# Edin_Usher_V2_0_discreto.net
KiCad netlist of a schematic drawn in EAGLE
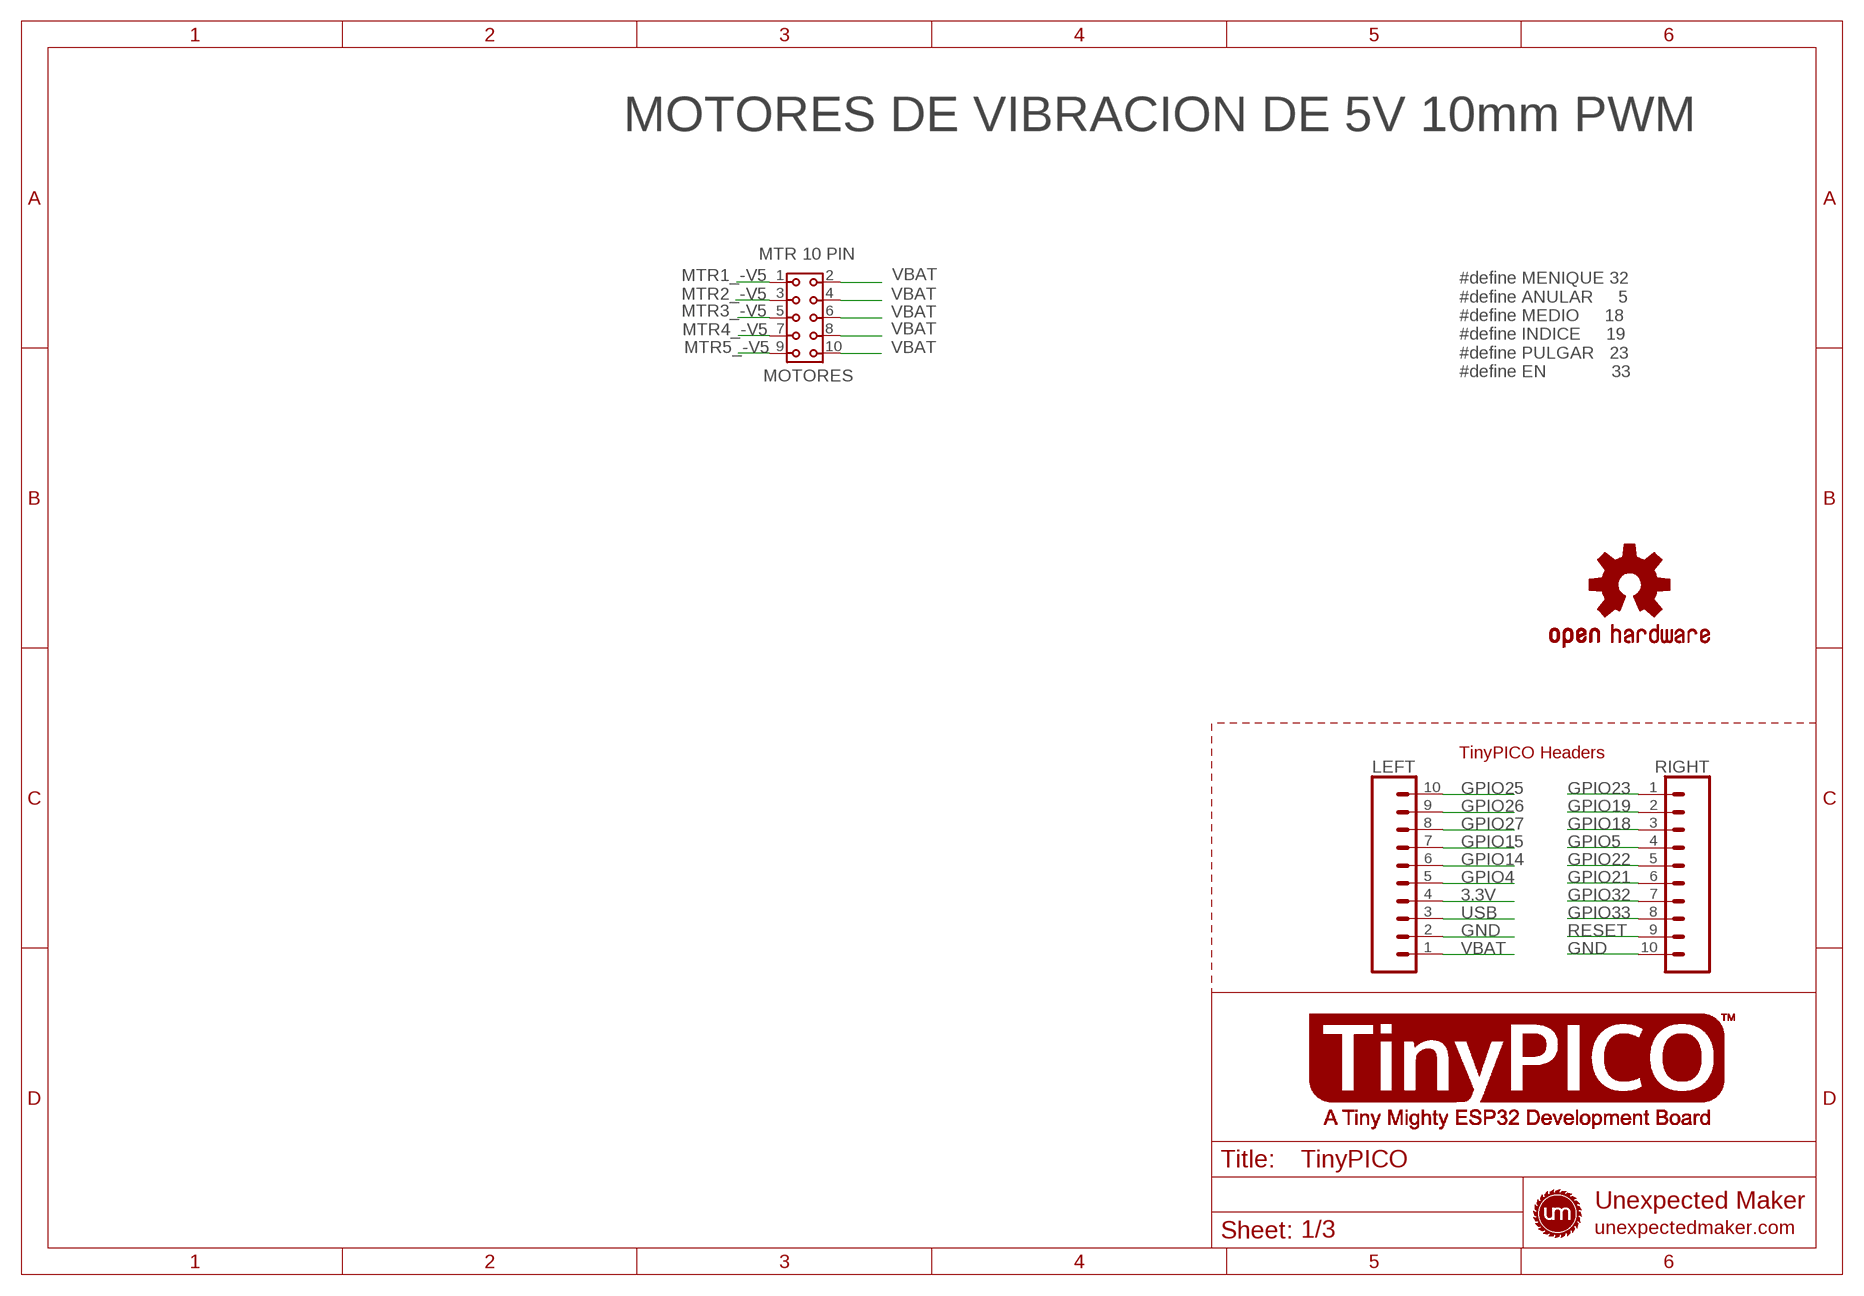
[diagram p0: schematic, sheet 1]
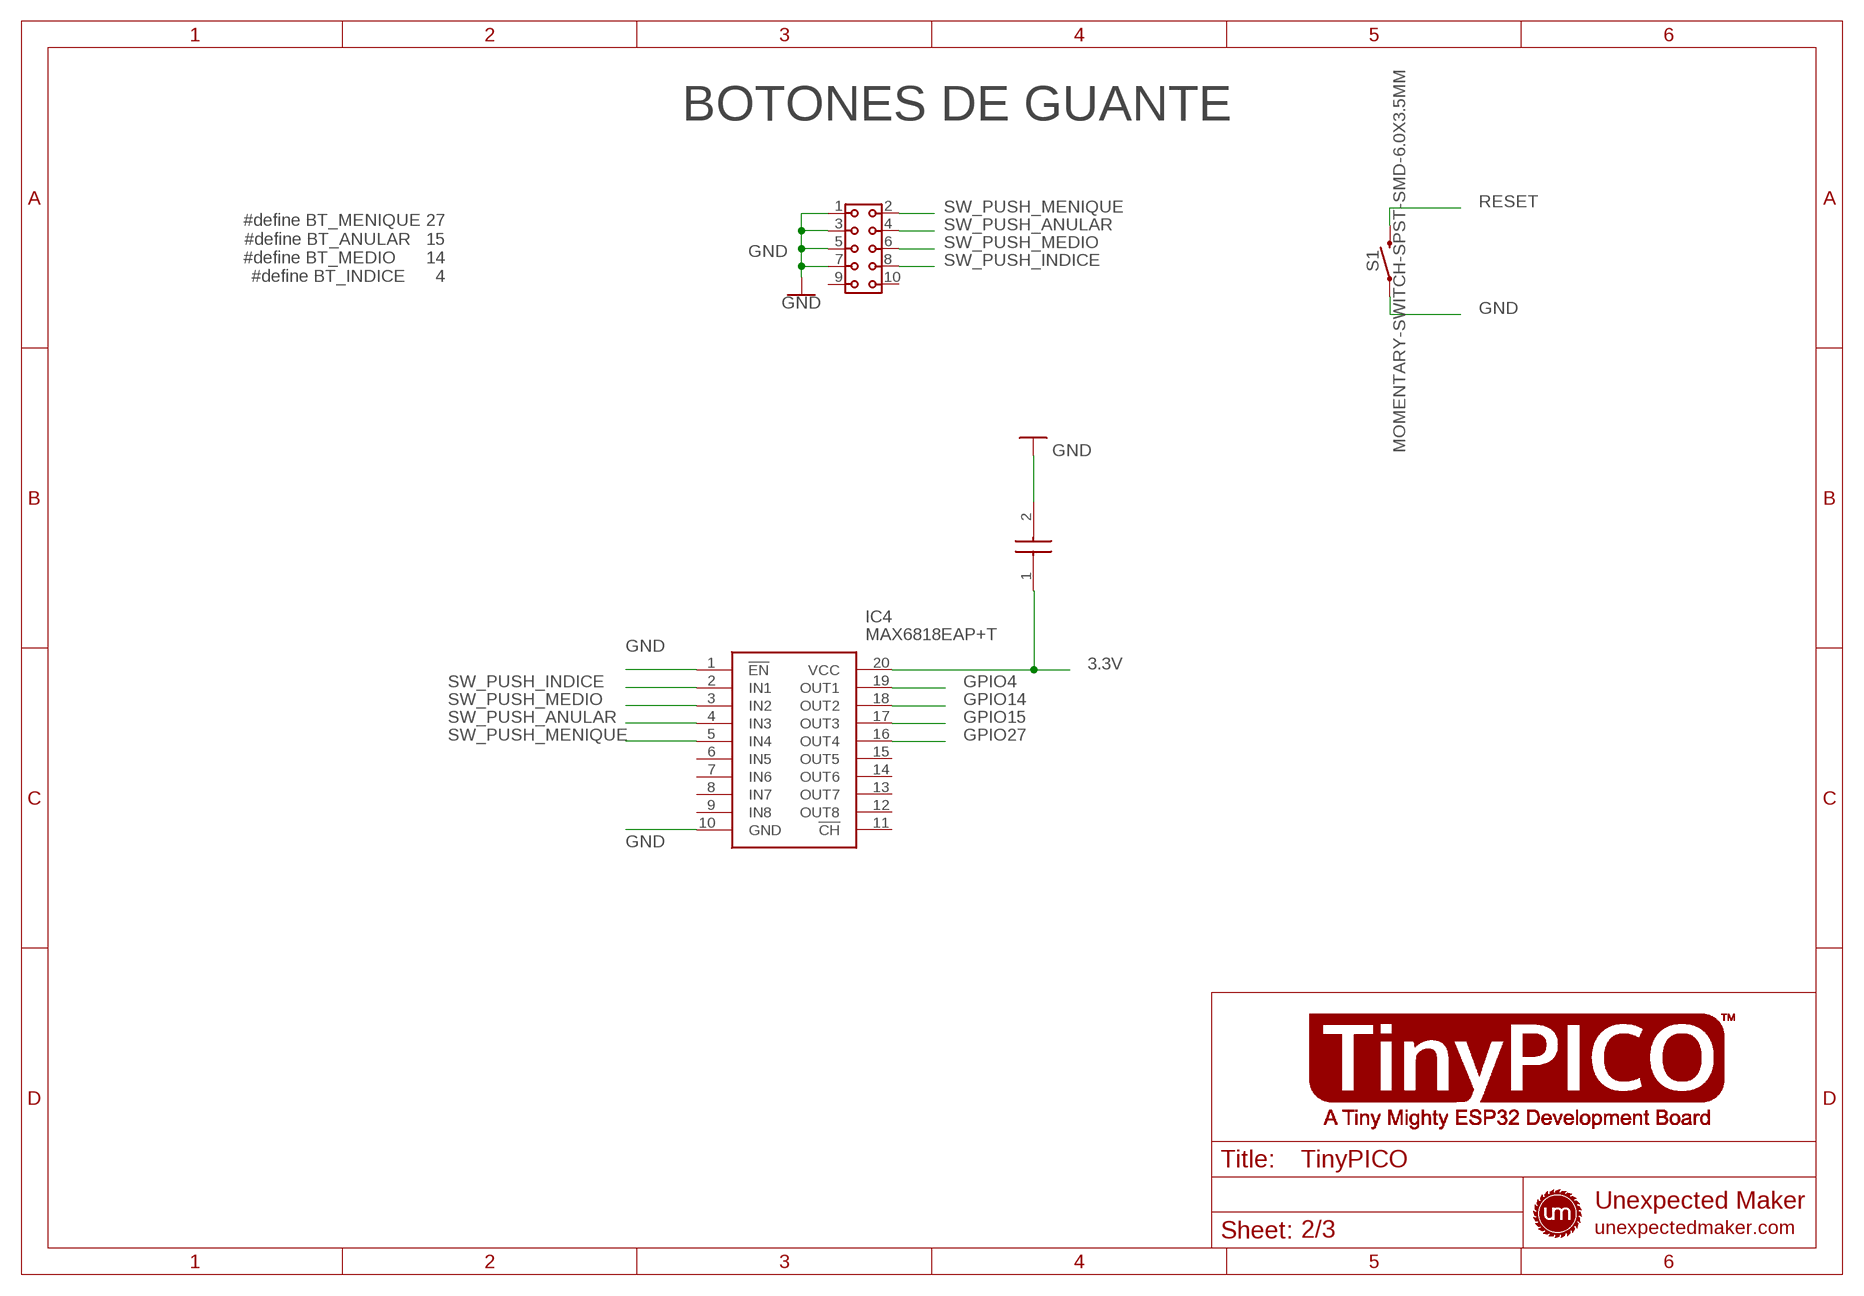
[diagram p1: schematic, sheet 2]
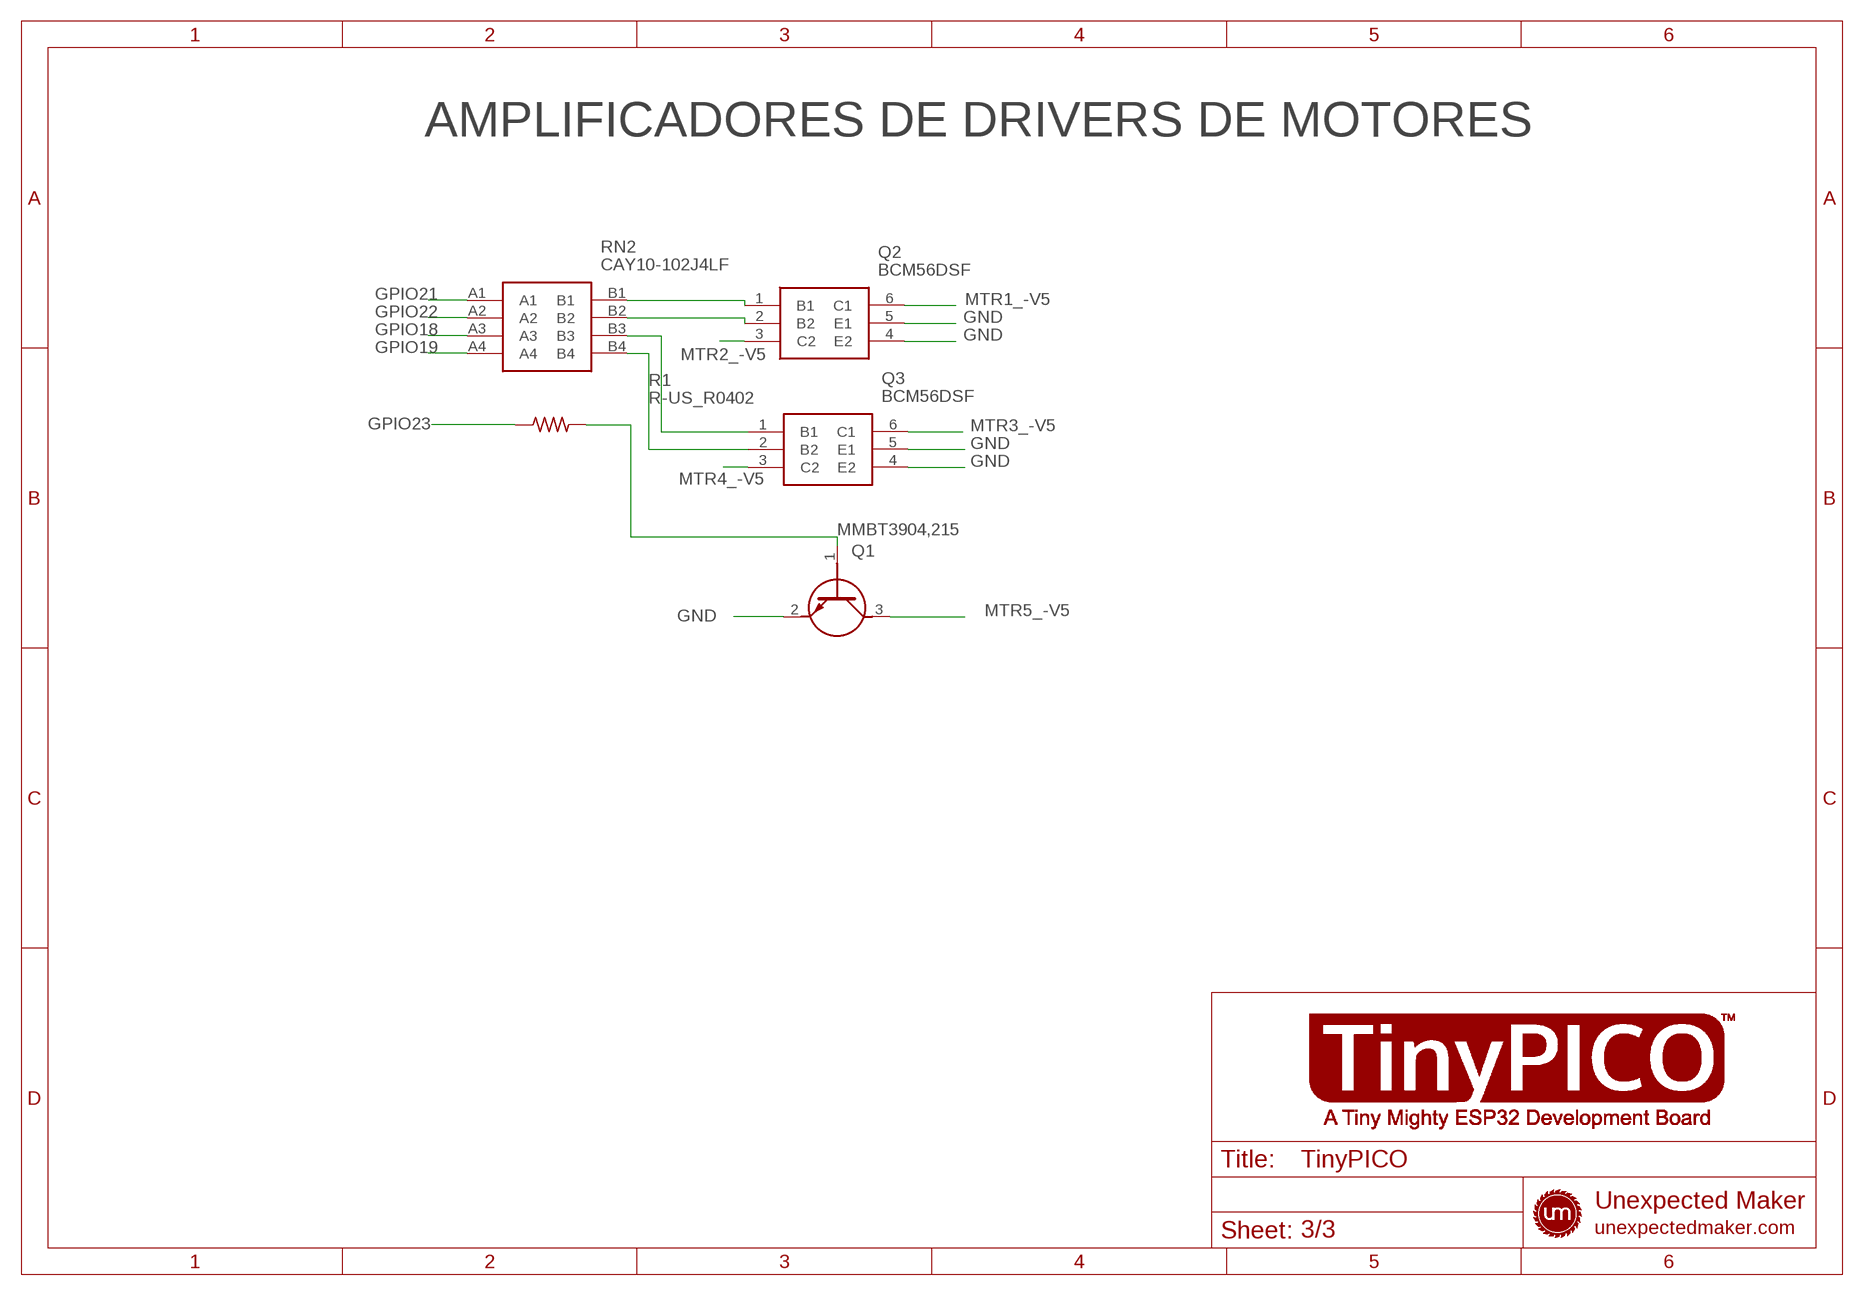
[diagram p2: schematic, sheet 3]

(export (version "E")
  (design (tool "Eeschema 10.0.6"))
  (components
    (comp (ref "LEFT")
      (value "TINYPICO_HEADER_10NO_SILK_PTH_FEMALE")
      (footprint "eagle-import:1X10_NO_SILK")
      (libsource (lib "eagle-import") (part "TINYPICO_HEADER_10NO_SILK_PTH_FEMALE"))
    )
    (comp (ref "LOGO1")
      (value "OSHW-LOGOS")
      (footprint "eagle-import:OSHW-LOGO-S")
      (libsource (lib "eagle-import") (part "OSHW-LOGOS"))
    )
    (comp (ref "MOTORES")
      (value "MTR 10 PIN")
      (footprint "eagle-import:61301021821")
      (libsource (lib "eagle-import") (part "6130XX21821_61301021821"))
    )
    (comp (ref "RIGHT")
      (value "TINYPICO_HEADER_10NO_SILK_PTH_FEMALE")
      (footprint "eagle-import:1X10_NO_SILK")
      (libsource (lib "eagle-import") (part "TINYPICO_HEADER_10NO_SILK_PTH_FEMALE"))
    )
    (comp (ref "BOTONES")
      (value "BTN 10 PIN")
      (footprint "eagle-import:61301021821")
      (libsource (lib "eagle-import") (part "6130XX21821_61301021821"))
    )
    (comp (ref "C8")
      (value "0603B104K160CT")
      (footprint "eagle-import:CAPC1608X87N")
      (fields (field (name "MOUSER_PART_NUMBER") "791-0603B104K160CT"))
      (libsource (lib "eagle-import") (part "0603B104K160CT"))
    )
    (comp (ref "IC4")
      (value "MAX6818EAP+T")
      (footprint "eagle-import:SOP65P778X199-20N")
      (fields (field (name "MOUSER_PART_NUMBER") "700-MAX6818EAPT"))
      (libsource (lib "eagle-import") (part "MAX6818EAP+T"))
    )
    (comp (ref "S1")
      (value "MOMENTARY-SWITCH-SPST-SMD-6.0X3.5MM")
      (footprint "eagle-import:TACTILE_SWITCH_SMD_6.0X3.5MM")
      (libsource (lib "eagle-import") (part "MOMENTARY-SWITCH-SPST-SMD-6.0X3.5MM"))
    )
    (comp (ref "Q1")
      (value "MMBT3904,215")
      (footprint "eagle-import:SOT95P230X110-3N")
      (fields (field (name "MOUSER_PART_NUMBER") "771-MMBT3904T/R"))
      (libsource (lib "eagle-import") (part "MMBT3904,215"))
    )
    (comp (ref "Q2")
      (value "BCM56DSF")
      (footprint "eagle-import:SOT95P275X110-6N")
      (fields (field (name "MOUSER_PART_NUMBER") "771-BCM56DSF"))
      (libsource (lib "eagle-import") (part "BCM56DSF"))
    )
    (comp (ref "Q3")
      (value "BCM56DSF")
      (footprint "eagle-import:SOT95P275X110-6N")
      (fields (field (name "MOUSER_PART_NUMBER") "771-BCM56DSF"))
      (libsource (lib "eagle-import") (part "BCM56DSF"))
    )
    (comp (ref "R1")
      (value "R-US_R0402")
      (footprint "eagle-import:R0402")
      (libsource (lib "eagle-import") (part "R-US_R0402"))
    )
    (comp (ref "RN2")
      (value "CAY10-102J4LF")
      (footprint "eagle-import:CAY10102J4LF")
      (fields (field (name "MOUSER_PART_NUMBER") "652-CAY10-102J4LF"))
      (libsource (lib "eagle-import") (part "CAY10-102J4LF"))
    )
  )
  (nets
    (net (code "1") (name "3.3V") (class "Default")
      (node (ref "C8") (pin "1") (pinfunction "1_1") (pintype "bidirectional"))
      (node (ref "IC4") (pin "20") (pinfunction "VCC_20") (pintype "power_in"))
      (node (ref "LEFT") (pin "4") (pinfunction "4_4") (pintype "passive"))
    )
    (net (code "2") (name "GND") (class "Default")
      (node (ref "BOTONES") (pin "1") (pinfunction "1_1") (pintype "passive"))
      (node (ref "BOTONES") (pin "3") (pinfunction "3_3") (pintype "passive"))
      (node (ref "BOTONES") (pin "5") (pinfunction "5_5") (pintype "passive"))
      (node (ref "BOTONES") (pin "7") (pinfunction "7_7") (pintype "passive"))
      (node (ref "C8") (pin "2") (pinfunction "2_2") (pintype "bidirectional"))
      (node (ref "IC4") (pin "1") (pinfunction "~{EN}_1") (pintype "input"))
      (node (ref "IC4") (pin "10") (pinfunction "GND_10") (pintype "power_in"))
      (node (ref "LEFT") (pin "2") (pinfunction "2_2") (pintype "passive"))
      (node (ref "Q1") (pin "2") (pinfunction "E_2") (pintype "bidirectional"))
      (node (ref "Q2") (pin "4") (pinfunction "E2_4") (pintype "bidirectional"))
      (node (ref "Q2") (pin "5") (pinfunction "E1_5") (pintype "bidirectional"))
      (node (ref "Q3") (pin "4") (pinfunction "E2_4") (pintype "bidirectional"))
      (node (ref "Q3") (pin "5") (pinfunction "E1_5") (pintype "bidirectional"))
      (node (ref "RIGHT") (pin "10") (pinfunction "10_10") (pintype "passive"))
      (node (ref "S1") (pin "1") (pinfunction "1_1") (pintype "passive"))
    )
    (net (code "3") (name "GPIO4") (class "Default")
      (node (ref "IC4") (pin "19") (pinfunction "OUT1_19") (pintype "output"))
      (node (ref "LEFT") (pin "5") (pinfunction "5_5") (pintype "passive"))
    )
    (net (code "4") (name "GPIO5") (class "Default")
      (node (ref "RIGHT") (pin "4") (pinfunction "4_4") (pintype "passive"))
    )
    (net (code "5") (name "GPIO14") (class "Default")
      (node (ref "IC4") (pin "18") (pinfunction "OUT2_18") (pintype "output"))
      (node (ref "LEFT") (pin "6") (pinfunction "6_6") (pintype "passive"))
    )
    (net (code "6") (name "GPIO15") (class "Default")
      (node (ref "IC4") (pin "17") (pinfunction "OUT3_17") (pintype "output"))
      (node (ref "LEFT") (pin "7") (pinfunction "7_7") (pintype "passive"))
    )
    (net (code "7") (name "GPIO18") (class "Default")
      (node (ref "RIGHT") (pin "3") (pinfunction "3_3") (pintype "passive"))
      (node (ref "RN2") (pin "A3") (pinfunction "A3_A3") (pintype "bidirectional"))
    )
    (net (code "8") (name "GPIO19") (class "Default")
      (node (ref "RIGHT") (pin "2") (pinfunction "2_2") (pintype "passive"))
      (node (ref "RN2") (pin "A4") (pinfunction "A4_A4") (pintype "bidirectional"))
    )
    (net (code "9") (name "GPIO21") (class "Default")
      (node (ref "RIGHT") (pin "6") (pinfunction "6_6") (pintype "passive"))
      (node (ref "RN2") (pin "A1") (pinfunction "A1_A1") (pintype "bidirectional"))
    )
    (net (code "10") (name "GPIO22") (class "Default")
      (node (ref "RIGHT") (pin "5") (pinfunction "5_5") (pintype "passive"))
      (node (ref "RN2") (pin "A2") (pinfunction "A2_A2") (pintype "bidirectional"))
    )
    (net (code "11") (name "GPIO23") (class "Default")
      (node (ref "R1") (pin "1") (pinfunction "1_1") (pintype "passive"))
      (node (ref "RIGHT") (pin "1") (pinfunction "1_1") (pintype "passive"))
    )
    (net (code "12") (name "GPIO25") (class "Default")
      (node (ref "LEFT") (pin "10") (pinfunction "10_10") (pintype "passive"))
    )
    (net (code "13") (name "GPIO26") (class "Default")
      (node (ref "LEFT") (pin "9") (pinfunction "9_9") (pintype "passive"))
    )
    (net (code "14") (name "GPIO27") (class "Default")
      (node (ref "IC4") (pin "16") (pinfunction "OUT4_16") (pintype "output"))
      (node (ref "LEFT") (pin "8") (pinfunction "8_8") (pintype "passive"))
    )
    (net (code "15") (name "GPIO32") (class "Default")
      (node (ref "RIGHT") (pin "7") (pinfunction "7_7") (pintype "passive"))
    )
    (net (code "16") (name "GPIO33") (class "Default")
      (node (ref "RIGHT") (pin "8") (pinfunction "8_8") (pintype "passive"))
    )
    (net (code "17") (name "MTR1_-V5") (class "Default")
      (node (ref "MOTORES") (pin "1") (pinfunction "1_1") (pintype "passive"))
      (node (ref "Q2") (pin "6") (pinfunction "C1_6") (pintype "bidirectional"))
    )
    (net (code "18") (name "MTR2_-V5") (class "Default")
      (node (ref "MOTORES") (pin "3") (pinfunction "3_3") (pintype "passive"))
      (node (ref "Q2") (pin "3") (pinfunction "C2_3") (pintype "bidirectional"))
    )
    (net (code "19") (name "MTR3_-V5") (class "Default")
      (node (ref "MOTORES") (pin "5") (pinfunction "5_5") (pintype "passive"))
      (node (ref "Q3") (pin "6") (pinfunction "C1_6") (pintype "bidirectional"))
    )
    (net (code "20") (name "MTR4_-V5") (class "Default")
      (node (ref "MOTORES") (pin "7") (pinfunction "7_7") (pintype "passive"))
      (node (ref "Q3") (pin "3") (pinfunction "C2_3") (pintype "bidirectional"))
    )
    (net (code "21") (name "MTR5_-V5") (class "Default")
      (node (ref "MOTORES") (pin "9") (pinfunction "9_9") (pintype "passive"))
      (node (ref "Q1") (pin "3") (pinfunction "C_3") (pintype "bidirectional"))
    )
    (net (code "22") (name "Net-(Q1-B)") (class "Default")
      (node (ref "Q1") (pin "1") (pinfunction "B_1") (pintype "bidirectional"))
      (node (ref "R1") (pin "2") (pinfunction "2_2") (pintype "passive"))
    )
    (net (code "23") (name "Net-(Q2-B1)") (class "Default")
      (node (ref "Q2") (pin "1") (pinfunction "B1_1") (pintype "bidirectional"))
      (node (ref "RN2") (pin "B1") (pinfunction "B1_B1") (pintype "bidirectional"))
    )
    (net (code "24") (name "Net-(Q2-B2)") (class "Default")
      (node (ref "Q2") (pin "2") (pinfunction "B2_2") (pintype "bidirectional"))
      (node (ref "RN2") (pin "B2") (pinfunction "B2_B2") (pintype "bidirectional"))
    )
    (net (code "25") (name "Net-(Q3-B1)") (class "Default")
      (node (ref "Q3") (pin "1") (pinfunction "B1_1") (pintype "bidirectional"))
      (node (ref "RN2") (pin "B3") (pinfunction "B3_B3") (pintype "bidirectional"))
    )
    (net (code "26") (name "Net-(Q3-B2)") (class "Default")
      (node (ref "Q3") (pin "2") (pinfunction "B2_2") (pintype "bidirectional"))
      (node (ref "RN2") (pin "B4") (pinfunction "B4_B4") (pintype "bidirectional"))
    )
    (net (code "27") (name "RESET") (class "Default")
      (node (ref "RIGHT") (pin "9") (pinfunction "9_9") (pintype "passive"))
      (node (ref "S1") (pin "2") (pinfunction "2_2") (pintype "passive"))
    )
    (net (code "28") (name "SW_PUSH_ANULAR") (class "Default")
      (node (ref "BOTONES") (pin "4") (pinfunction "4_4") (pintype "passive"))
      (node (ref "IC4") (pin "4") (pinfunction "IN3_4") (pintype "input"))
    )
    (net (code "29") (name "SW_PUSH_INDICE") (class "Default")
      (node (ref "BOTONES") (pin "8") (pinfunction "8_8") (pintype "passive"))
      (node (ref "IC4") (pin "2") (pinfunction "IN1_2") (pintype "input"))
    )
    (net (code "30") (name "SW_PUSH_MEDIO") (class "Default")
      (node (ref "BOTONES") (pin "6") (pinfunction "6_6") (pintype "passive"))
      (node (ref "IC4") (pin "3") (pinfunction "IN2_3") (pintype "input"))
    )
    (net (code "31") (name "SW_PUSH_MENIQUE") (class "Default")
      (node (ref "BOTONES") (pin "2") (pinfunction "2_2") (pintype "passive"))
      (node (ref "IC4") (pin "5") (pinfunction "IN4_5") (pintype "input"))
    )
    (net (code "32") (name "USB") (class "Default")
      (node (ref "LEFT") (pin "3") (pinfunction "3_3") (pintype "passive"))
    )
    (net (code "33") (name "VBAT") (class "Default")
      (node (ref "LEFT") (pin "1") (pinfunction "1_1") (pintype "passive"))
      (node (ref "MOTORES") (pin "10") (pinfunction "10_10") (pintype "passive"))
      (node (ref "MOTORES") (pin "2") (pinfunction "2_2") (pintype "passive"))
      (node (ref "MOTORES") (pin "4") (pinfunction "4_4") (pintype "passive"))
      (node (ref "MOTORES") (pin "6") (pinfunction "6_6") (pintype "passive"))
      (node (ref "MOTORES") (pin "8") (pinfunction "8_8") (pintype "passive"))
    )
    (net (code "34") (name "unconnected-(BOTONES-Pad9)") (class "Default")
      (node (ref "BOTONES") (pin "9") (pinfunction "9_9") (pintype "passive"))
    )
    (net (code "35") (name "unconnected-(BOTONES-Pad10)") (class "Default")
      (node (ref "BOTONES") (pin "10") (pinfunction "10_10") (pintype "passive"))
    )
    (net (code "36") (name "unconnected-(IC4-IN5-Pad6)") (class "Default")
      (node (ref "IC4") (pin "6") (pinfunction "IN5_6") (pintype "input"))
    )
    (net (code "37") (name "unconnected-(IC4-IN6-Pad7)") (class "Default")
      (node (ref "IC4") (pin "7") (pinfunction "IN6_7") (pintype "input"))
    )
    (net (code "38") (name "unconnected-(IC4-IN7-Pad8)") (class "Default")
      (node (ref "IC4") (pin "8") (pinfunction "IN7_8") (pintype "input"))
    )
    (net (code "39") (name "unconnected-(IC4-IN8-Pad9)") (class "Default")
      (node (ref "IC4") (pin "9") (pinfunction "IN8_9") (pintype "input"))
    )
    (net (code "40") (name "unconnected-(IC4-OUT5-Pad15)") (class "Default")
      (node (ref "IC4") (pin "15") (pinfunction "OUT5_15") (pintype "output"))
    )
    (net (code "41") (name "unconnected-(IC4-OUT6-Pad14)") (class "Default")
      (node (ref "IC4") (pin "14") (pinfunction "OUT6_14") (pintype "output"))
    )
    (net (code "42") (name "unconnected-(IC4-OUT7-Pad13)") (class "Default")
      (node (ref "IC4") (pin "13") (pinfunction "OUT7_13") (pintype "output"))
    )
    (net (code "43") (name "unconnected-(IC4-OUT8-Pad12)") (class "Default")
      (node (ref "IC4") (pin "12") (pinfunction "OUT8_12") (pintype "output"))
    )
    (net (code "44") (name "unconnected-(IC4-~{CH}-Pad11)") (class "Default")
      (node (ref "IC4") (pin "11") (pinfunction "~{CH}_11") (pintype "output"))
    )
  )
)
